# SBC_65C02_ISA_Discrete_v1.net
KiCad netlist of a schematic drawn in EAGLE
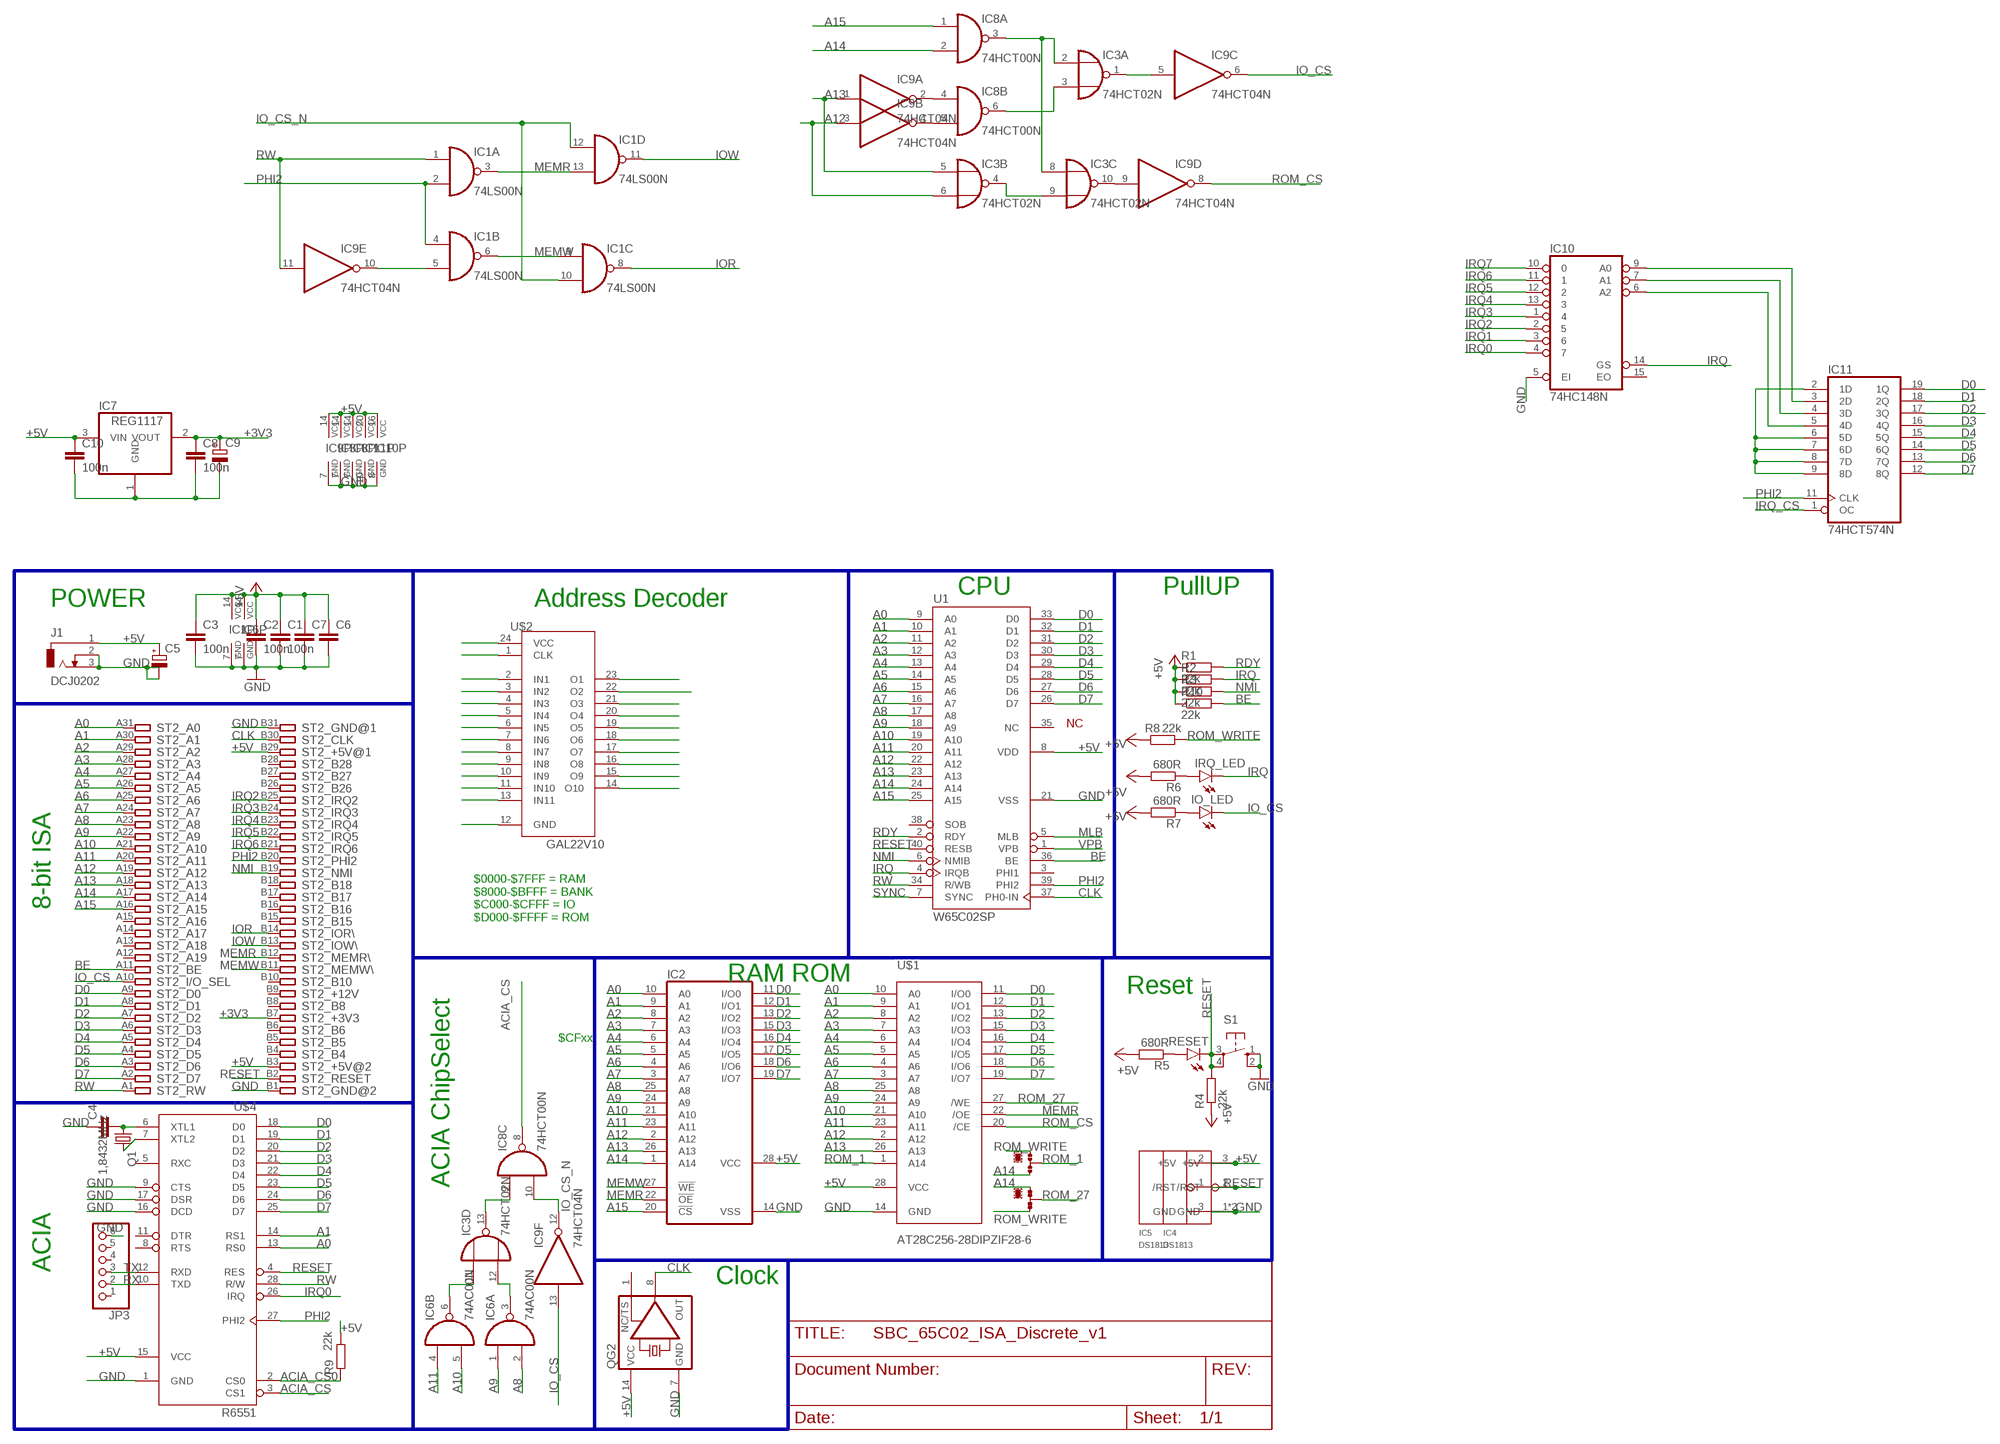
[diagram p0: schematic, sheet 1]

(export (version "E")
  (design (tool "Eeschema 10.0.6"))
  (components
    (comp (ref "C1")
      (value "100n")
      (footprint "eagle-import:C050-025X075")
      (libsource (lib "eagle-import") (part "C-EU050-025X075"))
    )
    (comp (ref "C2")
      (value "100n")
      (footprint "eagle-import:C050-025X075")
      (libsource (lib "eagle-import") (part "C-EU050-025X075"))
    )
    (comp (ref "C3")
      (value "100n")
      (footprint "eagle-import:C050-025X075")
      (libsource (lib "eagle-import") (part "C-EU050-025X075"))
    )
    (comp (ref "C4")
      (value "C-EU025-030X050")
      (footprint "eagle-import:C025-030X050")
      (libsource (lib "eagle-import") (part "rcl_334_C-EU025-030X050"))
    )
    (comp (ref "C5")
      (value "CPOL-EUE3.5-8")
      (footprint "eagle-import:E3,5-8")
      (libsource (lib "eagle-import") (part "CPOL-EUE3.5-8"))
    )
    (comp (ref "C6")
      (value "C-EU050-035X075")
      (footprint "eagle-import:C050-035X075")
      (libsource (lib "eagle-import") (part "rcl_334_C-EU050-035X075"))
    )
    (comp (ref "C7")
      (value "C-EU050-035X075")
      (footprint "eagle-import:C050-035X075")
      (libsource (lib "eagle-import") (part "rcl_334_C-EU050-035X075"))
    )
    (comp (ref "C8")
      (value "100n")
      (footprint "eagle-import:C050-025X075")
      (libsource (lib "eagle-import") (part "C-EU050-025X075"))
    )
    (comp (ref "C9")
      (value "CPOL-EUE3.5-8")
      (footprint "eagle-import:E3,5-8")
      (libsource (lib "eagle-import") (part "CPOL-EUE3.5-8"))
    )
    (comp (ref "C10")
      (value "100n")
      (footprint "eagle-import:C050-025X075")
      (libsource (lib "eagle-import") (part "C-EU050-025X075"))
    )
    (comp (ref "IC1")
      (value "74LS00N")
      (footprint "eagle-import:DIL14")
      (libsource (lib "eagle-import") (part "7400NLS"))
    )
    (comp (ref "IC2")
      (value "62256P")
      (footprint "eagle-import:DIL28-6")
      (libsource (lib "eagle-import") (part "62256P"))
    )
    (comp (ref "IC3")
      (value "74HCT02N")
      (footprint "eagle-import:DIL14")
      (libsource (lib "eagle-import") (part "7402NHCT"))
    )
    (comp (ref "IC4")
      (value "DS1813")
      (footprint "eagle-import:SOT223")
      (libsource (lib "eagle-import") (part "DS1813SOT-223"))
    )
    (comp (ref "IC5")
      (value "DS1813")
      (footprint "eagle-import:TO-92")
      (libsource (lib "eagle-import") (part "DS1813"))
    )
    (comp (ref "IC6")
      (value "74AC00N")
      (footprint "eagle-import:DIL14")
      (libsource (lib "eagle-import") (part "7400NAC"))
    )
    (comp (ref "IC7")
      (value "REG1117")
      (footprint "eagle-import:SOT223")
      (libsource (lib "eagle-import") (part "REG1117"))
    )
    (comp (ref "IC8")
      (value "74HCT00N")
      (footprint "eagle-import:DIL14")
      (libsource (lib "eagle-import") (part "7400NHCT"))
    )
    (comp (ref "IC9")
      (value "74HCT04N")
      (footprint "eagle-import:DIL14")
      (libsource (lib "eagle-import") (part "7404NHCT"))
    )
    (comp (ref "IC10")
      (value "74HC148N")
      (footprint "eagle-import:DIL16")
      (libsource (lib "eagle-import") (part "74148NHC"))
    )
    (comp (ref "IC11")
      (value "74HCT574N")
      (footprint "eagle-import:DIL20")
      (libsource (lib "eagle-import") (part "74574NHCT"))
    )
    (comp (ref "IO_LED")
      (value "LED5MM")
      (footprint "eagle-import:LED5MM")
      (libsource (lib "eagle-import") (part "LED5MM"))
    )
    (comp (ref "IRQ_LED")
      (value "LED5MM")
      (footprint "eagle-import:LED5MM")
      (libsource (lib "eagle-import") (part "LED5MM"))
    )
    (comp (ref "J1")
      (value "DCJ0202")
      (footprint "eagle-import:DCJ0202")
      (libsource (lib "eagle-import") (part "DCJ0202"))
    )
    (comp (ref "JP3")
      (value "PINHD-1X6/90")
      (footprint "eagle-import:1X06_90")
      (libsource (lib "eagle-import") (part "PINHD-1X6/90"))
    )
    (comp (ref "Q1")
      (value "1,8432MHz")
      (footprint "eagle-import:HC49_S")
      (libsource (lib "eagle-import") (part "CRYSTALHC49S"))
    )
    (comp (ref "QG2")
      (value "XO-14")
      (footprint "eagle-import:DIL14S")
      (libsource (lib "eagle-import") (part "XO-14"))
    )
    (comp (ref "R1")
      (value "22k")
      (footprint "eagle-import:0207_10")
      (libsource (lib "eagle-import") (part "R-EU_0207/10"))
    )
    (comp (ref "R2")
      (value "22k")
      (footprint "eagle-import:0207_10")
      (libsource (lib "eagle-import") (part "R-EU_0207/10"))
    )
    (comp (ref "R3")
      (value "22k")
      (footprint "eagle-import:0207_10")
      (libsource (lib "eagle-import") (part "R-EU_0207/10"))
    )
    (comp (ref "R4")
      (value "22k")
      (footprint "eagle-import:0207_10")
      (libsource (lib "eagle-import") (part "resistor_348_R-EU_0207/10"))
    )
    (comp (ref "R5")
      (value "680R")
      (footprint "eagle-import:0207_10")
      (libsource (lib "eagle-import") (part "resistor_348_R-EU_0207/10"))
    )
    (comp (ref "R6")
      (value "680R")
      (footprint "eagle-import:0207_10")
      (libsource (lib "eagle-import") (part "resistor_348_R-EU_0207/10"))
    )
    (comp (ref "R7")
      (value "680R")
      (footprint "eagle-import:0207_10")
      (libsource (lib "eagle-import") (part "resistor_348_R-EU_0207/10"))
    )
    (comp (ref "R8")
      (value "22k")
      (footprint "eagle-import:0207_10")
      (libsource (lib "eagle-import") (part "rcl_334_R-EU_0207/10"))
    )
    (comp (ref "R9")
      (value "22k")
      (footprint "eagle-import:0207_10")
      (libsource (lib "eagle-import") (part "rcl_334_R-EU_0207/10"))
    )
    (comp (ref "R10")
      (value "22k")
      (footprint "eagle-import:0207_10")
      (libsource (lib "eagle-import") (part "R-EU_0207/10"))
    )
    (comp (ref "RESET")
      (value "LED5MM")
      (footprint "eagle-import:LED5MM")
      (libsource (lib "eagle-import") (part "LED5MM"))
    )
    (comp (ref "ROM_1")
      (value "0R-JUMPA")
      (footprint "eagle-import:A0R-JMP")
      (libsource (lib "eagle-import") (part "0R-JUMPA"))
    )
    (comp (ref "ROM_27")
      (value "0R-JUMPA")
      (footprint "eagle-import:A0R-JMP")
      (libsource (lib "eagle-import") (part "0R-JUMPA"))
    )
    (comp (ref "S1")
      (value "10-XX")
      (footprint "eagle-import:B3F-10XX")
      (fields (field (name "MPN") "B3F-1000"))
      (libsource (lib "eagle-import") (part "10-XX"))
    )
    (comp (ref "ST2")
      (value "IBM8BIT_ISA")
      (footprint "eagle-import:IBM8BIT")
      (libsource (lib "eagle-import") (part "IBM8BIT_ISA"))
    )
    (comp (ref "U$1")
      (value "AT28C256-28DIPZIF28-6")
      (footprint "eagle-import:228-1277-00-0602J")
      (libsource (lib "eagle-import") (part "AT28C256-28DIPZIF28-6"))
    )
    (comp (ref "U$2")
      (value "GAL22V10")
      (footprint "eagle-import:DIL28_1")
      (libsource (lib "eagle-import") (part "GAL22V10"))
    )
    (comp (ref "U$4")
      (value "R6551")
      (footprint "eagle-import:DIP-28")
      (libsource (lib "eagle-import") (part "R6551"))
    )
    (comp (ref "U1")
      (value "W65C02SP")
      (footprint "eagle-import:DIP-40")
      (libsource (lib "eagle-import") (part "W65C02SP"))
    )
  )
  (nets
    (net (code "1") (name "+5V") (class "Default")
      (node (ref "C1") (pin "1") (pinfunction "1_1") (pintype "passive"))
      (node (ref "C10") (pin "1") (pinfunction "1_1") (pintype "passive"))
      (node (ref "C2") (pin "1") (pinfunction "1_1") (pintype "passive"))
      (node (ref "C3") (pin "1") (pinfunction "1_1") (pintype "passive"))
      (node (ref "C5") (pin "+") (pinfunction "+_+") (pintype "passive"))
      (node (ref "C6") (pin "1") (pinfunction "1_1") (pintype "passive"))
      (node (ref "C7") (pin "1") (pinfunction "1_1") (pintype "passive"))
      (node (ref "IC1") (pin "14") (pinfunction "VCC_14") (pintype "power_in"))
      (node (ref "IC10") (pin "16") (pinfunction "VCC_16") (pintype "power_in"))
      (node (ref "IC11") (pin "20") (pinfunction "VCC_20") (pintype "power_in"))
      (node (ref "IC2") (pin "28") (pinfunction "VCC_28") (pintype "power_in"))
      (node (ref "IC3") (pin "14") (pinfunction "VCC_14") (pintype "power_in"))
      (node (ref "IC4") (pin "3") (pinfunction "+5V_3") (pintype "power_in"))
      (node (ref "IC5") (pin "2") (pinfunction "+5V_2") (pintype "power_in"))
      (node (ref "IC6") (pin "14") (pinfunction "VCC_14") (pintype "power_in"))
      (node (ref "IC7") (pin "3") (pinfunction "VIN_3") (pintype "input"))
      (node (ref "IC8") (pin "14") (pinfunction "VCC_14") (pintype "power_in"))
      (node (ref "IC9") (pin "14") (pinfunction "VCC_14") (pintype "power_in"))
      (node (ref "J1") (pin "1") (pinfunction "1_1") (pintype "passive"))
      (node (ref "QG2") (pin "14") (pinfunction "VCC_14") (pintype "power_in"))
      (node (ref "R1") (pin "1") (pinfunction "1_1") (pintype "passive"))
      (node (ref "R10") (pin "1") (pinfunction "1_1") (pintype "passive"))
      (node (ref "R2") (pin "1") (pinfunction "1_1") (pintype "passive"))
      (node (ref "R3") (pin "1") (pinfunction "1_1") (pintype "passive"))
      (node (ref "R4") (pin "1") (pinfunction "1_1") (pintype "passive"))
      (node (ref "R5") (pin "2") (pinfunction "2_2") (pintype "passive"))
      (node (ref "R6") (pin "2") (pinfunction "2_2") (pintype "passive"))
      (node (ref "R7") (pin "2") (pinfunction "2_2") (pintype "passive"))
      (node (ref "R8") (pin "1") (pinfunction "1_1") (pintype "passive"))
      (node (ref "R9") (pin "2") (pinfunction "2_2") (pintype "passive"))
      (node (ref "ST2") (pin "B29") (pinfunction "P_B29") (pintype "bidirectional"))
      (node (ref "ST2") (pin "B3") (pinfunction "P_B3") (pintype "bidirectional"))
      (node (ref "U$1") (pin "28") (pinfunction "VCC_28") (pintype "bidirectional"))
      (node (ref "U$4") (pin "15") (pinfunction "VCC_15") (pintype "power_in"))
      (node (ref "U1") (pin "8") (pinfunction "VDD_8") (pintype "power_in"))
    )
    (net (code "2") (name "/+3V3") (class "Default")
      (node (ref "C8") (pin "1") (pinfunction "1_1") (pintype "passive"))
      (node (ref "C9") (pin "+") (pinfunction "+_+") (pintype "passive"))
      (node (ref "IC7") (pin "2") (pinfunction "VOUT_2") (pintype "output"))
      (node (ref "ST2") (pin "B7") (pinfunction "P_B7") (pintype "bidirectional"))
    )
    (net (code "3") (name "/A0") (class "Default")
      (node (ref "IC2") (pin "10") (pinfunction "A0_10") (pintype "input"))
      (node (ref "ST2") (pin "A31") (pinfunction "P_A31") (pintype "bidirectional"))
      (node (ref "U$1") (pin "10") (pinfunction "A0_10") (pintype "bidirectional"))
      (node (ref "U$4") (pin "13") (pinfunction "RS0_13") (pintype "input"))
      (node (ref "U1") (pin "9") (pinfunction "A0_9") (pintype "bidirectional"))
    )
    (net (code "4") (name "/A1") (class "Default")
      (node (ref "IC2") (pin "9") (pinfunction "A1_9") (pintype "input"))
      (node (ref "ST2") (pin "A30") (pinfunction "P_A30") (pintype "bidirectional"))
      (node (ref "U$1") (pin "9") (pinfunction "A1_9") (pintype "bidirectional"))
      (node (ref "U$4") (pin "14") (pinfunction "RS1_14") (pintype "input"))
      (node (ref "U1") (pin "10") (pinfunction "A1_10") (pintype "bidirectional"))
    )
    (net (code "5") (name "/A2") (class "Default")
      (node (ref "IC2") (pin "8") (pinfunction "A2_8") (pintype "input"))
      (node (ref "ST2") (pin "A29") (pinfunction "P_A29") (pintype "bidirectional"))
      (node (ref "U$1") (pin "8") (pinfunction "A2_8") (pintype "bidirectional"))
      (node (ref "U1") (pin "11") (pinfunction "A2_11") (pintype "bidirectional"))
    )
    (net (code "6") (name "/A3") (class "Default")
      (node (ref "IC2") (pin "7") (pinfunction "A3_7") (pintype "input"))
      (node (ref "ST2") (pin "A28") (pinfunction "P_A28") (pintype "bidirectional"))
      (node (ref "U$1") (pin "7") (pinfunction "A3_7") (pintype "bidirectional"))
      (node (ref "U1") (pin "12") (pinfunction "A3_12") (pintype "bidirectional"))
    )
    (net (code "7") (name "/A4") (class "Default")
      (node (ref "IC2") (pin "6") (pinfunction "A4_6") (pintype "input"))
      (node (ref "ST2") (pin "A27") (pinfunction "P_A27") (pintype "bidirectional"))
      (node (ref "U$1") (pin "6") (pinfunction "A4_6") (pintype "bidirectional"))
      (node (ref "U1") (pin "13") (pinfunction "A4_13") (pintype "bidirectional"))
    )
    (net (code "8") (name "/A5") (class "Default")
      (node (ref "IC2") (pin "5") (pinfunction "A5_5") (pintype "input"))
      (node (ref "ST2") (pin "A26") (pinfunction "P_A26") (pintype "bidirectional"))
      (node (ref "U$1") (pin "5") (pinfunction "A5_5") (pintype "bidirectional"))
      (node (ref "U1") (pin "14") (pinfunction "A5_14") (pintype "bidirectional"))
    )
    (net (code "9") (name "/A6") (class "Default")
      (node (ref "IC2") (pin "4") (pinfunction "A6_4") (pintype "input"))
      (node (ref "ST2") (pin "A25") (pinfunction "P_A25") (pintype "bidirectional"))
      (node (ref "U$1") (pin "4") (pinfunction "A6_4") (pintype "bidirectional"))
      (node (ref "U1") (pin "15") (pinfunction "A6_15") (pintype "bidirectional"))
    )
    (net (code "10") (name "/A7") (class "Default")
      (node (ref "IC2") (pin "3") (pinfunction "A7_3") (pintype "input"))
      (node (ref "ST2") (pin "A24") (pinfunction "P_A24") (pintype "bidirectional"))
      (node (ref "U$1") (pin "3") (pinfunction "A7_3") (pintype "bidirectional"))
      (node (ref "U1") (pin "16") (pinfunction "A7_16") (pintype "bidirectional"))
    )
    (net (code "11") (name "/A8") (class "Default")
      (node (ref "IC2") (pin "25") (pinfunction "A8_25") (pintype "input"))
      (node (ref "IC6") (pin "2") (pinfunction "I1_2") (pintype "input"))
      (node (ref "ST2") (pin "A23") (pinfunction "P_A23") (pintype "bidirectional"))
      (node (ref "U$1") (pin "25") (pinfunction "A8_25") (pintype "bidirectional"))
      (node (ref "U1") (pin "17") (pinfunction "A8_17") (pintype "bidirectional"))
    )
    (net (code "12") (name "/A9") (class "Default")
      (node (ref "IC2") (pin "24") (pinfunction "A9_24") (pintype "input"))
      (node (ref "IC6") (pin "1") (pinfunction "I0_1") (pintype "input"))
      (node (ref "ST2") (pin "A22") (pinfunction "P_A22") (pintype "bidirectional"))
      (node (ref "U$1") (pin "24") (pinfunction "A9_24") (pintype "bidirectional"))
      (node (ref "U1") (pin "18") (pinfunction "A9_18") (pintype "bidirectional"))
    )
    (net (code "13") (name "/A10") (class "Default")
      (node (ref "IC2") (pin "21") (pinfunction "A10_21") (pintype "input"))
      (node (ref "IC6") (pin "5") (pinfunction "I1_5") (pintype "input"))
      (node (ref "ST2") (pin "A21") (pinfunction "P_A21") (pintype "bidirectional"))
      (node (ref "U$1") (pin "21") (pinfunction "A10_21") (pintype "bidirectional"))
      (node (ref "U1") (pin "19") (pinfunction "A10_19") (pintype "bidirectional"))
    )
    (net (code "14") (name "/A11") (class "Default")
      (node (ref "IC2") (pin "23") (pinfunction "A11_23") (pintype "input"))
      (node (ref "IC6") (pin "4") (pinfunction "I0_4") (pintype "input"))
      (node (ref "ST2") (pin "A20") (pinfunction "P_A20") (pintype "bidirectional"))
      (node (ref "U$1") (pin "23") (pinfunction "A11_23") (pintype "bidirectional"))
      (node (ref "U1") (pin "20") (pinfunction "A11_20") (pintype "bidirectional"))
    )
    (net (code "15") (name "/A12") (class "Default")
      (node (ref "IC2") (pin "2") (pinfunction "A12_2") (pintype "input"))
      (node (ref "IC3") (pin "6") (pinfunction "I1_6") (pintype "input"))
      (node (ref "IC9") (pin "3") (pinfunction "I_3") (pintype "input"))
      (node (ref "ST2") (pin "A19") (pinfunction "P_A19") (pintype "bidirectional"))
      (node (ref "U$1") (pin "2") (pinfunction "A12_2") (pintype "bidirectional"))
      (node (ref "U1") (pin "22") (pinfunction "A12_22") (pintype "bidirectional"))
    )
    (net (code "16") (name "/A13") (class "Default")
      (node (ref "IC2") (pin "26") (pinfunction "A13_26") (pintype "input"))
      (node (ref "IC3") (pin "5") (pinfunction "I0_5") (pintype "input"))
      (node (ref "IC9") (pin "1") (pinfunction "I_1") (pintype "input"))
      (node (ref "ST2") (pin "A18") (pinfunction "P_A18") (pintype "bidirectional"))
      (node (ref "U$1") (pin "26") (pinfunction "A13_26") (pintype "bidirectional"))
      (node (ref "U1") (pin "23") (pinfunction "A13_23") (pintype "bidirectional"))
    )
    (net (code "17") (name "/A14") (class "Default")
      (node (ref "IC2") (pin "1") (pinfunction "A14_1") (pintype "input"))
      (node (ref "IC8") (pin "2") (pinfunction "I1_2") (pintype "input"))
      (node (ref "ROM_1") (pin "3") (pinfunction "3_3") (pintype "passive"))
      (node (ref "ROM_27") (pin "1") (pinfunction "1_1") (pintype "passive"))
      (node (ref "ST2") (pin "A17") (pinfunction "P_A17") (pintype "bidirectional"))
      (node (ref "U1") (pin "24") (pinfunction "A14_24") (pintype "bidirectional"))
    )
    (net (code "18") (name "/A15") (class "Default")
      (node (ref "IC2") (pin "20") (pinfunction "~{CS}_20") (pintype "input"))
      (node (ref "IC8") (pin "1") (pinfunction "I0_1") (pintype "input"))
      (node (ref "ST2") (pin "A16") (pinfunction "P_A16") (pintype "bidirectional"))
      (node (ref "U1") (pin "25") (pinfunction "A15_25") (pintype "bidirectional"))
    )
    (net (code "19") (name "/ACIA_CS") (class "Default")
      (node (ref "IC8") (pin "8") (pinfunction "O_8") (pintype "output"))
      (node (ref "U$4") (pin "3") (pinfunction "CS1_3") (pintype "input"))
    )
    (net (code "20") (name "/ACIA_CS0") (class "Default")
      (node (ref "R9") (pin "1") (pinfunction "1_1") (pintype "passive"))
      (node (ref "U$4") (pin "2") (pinfunction "CS0_2") (pintype "input"))
    )
    (net (code "21") (name "/BE") (class "Default")
      (node (ref "R10") (pin "2") (pinfunction "2_2") (pintype "passive"))
      (node (ref "ST2") (pin "A11") (pinfunction "P_A11") (pintype "bidirectional"))
      (node (ref "U1") (pin "36") (pinfunction "BE_36") (pintype "input"))
    )
    (net (code "22") (name "/CLK") (class "Default")
      (node (ref "QG2") (pin "8") (pinfunction "OUT_8") (pintype "output"))
      (node (ref "ST2") (pin "B30") (pinfunction "P_B30") (pintype "bidirectional"))
      (node (ref "U1") (pin "37") (pinfunction "PH0-IN_37") (pintype "input"))
    )
    (net (code "23") (name "/D0") (class "Default")
      (node (ref "IC11") (pin "19") (pinfunction "1Q_19") (pintype "tri_state"))
      (node (ref "IC2") (pin "11") (pinfunction "I/O0_11") (pintype "bidirectional"))
      (node (ref "ST2") (pin "A9") (pinfunction "P_A9") (pintype "bidirectional"))
      (node (ref "U$1") (pin "11") (pinfunction "I/O0_11") (pintype "bidirectional"))
      (node (ref "U$4") (pin "18") (pinfunction "D0_18") (pintype "bidirectional"))
      (node (ref "U1") (pin "33") (pinfunction "D0_33") (pintype "bidirectional"))
    )
    (net (code "24") (name "/D1") (class "Default")
      (node (ref "IC11") (pin "18") (pinfunction "2Q_18") (pintype "tri_state"))
      (node (ref "IC2") (pin "12") (pinfunction "I/O1_12") (pintype "bidirectional"))
      (node (ref "ST2") (pin "A8") (pinfunction "P_A8") (pintype "bidirectional"))
      (node (ref "U$1") (pin "12") (pinfunction "I/O1_12") (pintype "bidirectional"))
      (node (ref "U$4") (pin "19") (pinfunction "D1_19") (pintype "bidirectional"))
      (node (ref "U1") (pin "32") (pinfunction "D1_32") (pintype "bidirectional"))
    )
    (net (code "25") (name "/D2") (class "Default")
      (node (ref "IC11") (pin "17") (pinfunction "3Q_17") (pintype "tri_state"))
      (node (ref "IC2") (pin "13") (pinfunction "I/O2_13") (pintype "bidirectional"))
      (node (ref "ST2") (pin "A7") (pinfunction "P_A7") (pintype "bidirectional"))
      (node (ref "U$1") (pin "13") (pinfunction "I/O2_13") (pintype "bidirectional"))
      (node (ref "U$4") (pin "20") (pinfunction "D2_20") (pintype "bidirectional"))
      (node (ref "U1") (pin "31") (pinfunction "D2_31") (pintype "bidirectional"))
    )
    (net (code "26") (name "/D3") (class "Default")
      (node (ref "IC11") (pin "16") (pinfunction "4Q_16") (pintype "tri_state"))
      (node (ref "IC2") (pin "15") (pinfunction "I/O3_15") (pintype "bidirectional"))
      (node (ref "ST2") (pin "A6") (pinfunction "P_A6") (pintype "bidirectional"))
      (node (ref "U$1") (pin "15") (pinfunction "I/O3_15") (pintype "bidirectional"))
      (node (ref "U$4") (pin "21") (pinfunction "D3_21") (pintype "bidirectional"))
      (node (ref "U1") (pin "30") (pinfunction "D3_30") (pintype "bidirectional"))
    )
    (net (code "27") (name "/D4") (class "Default")
      (node (ref "IC11") (pin "15") (pinfunction "5Q_15") (pintype "tri_state"))
      (node (ref "IC2") (pin "16") (pinfunction "I/O4_16") (pintype "bidirectional"))
      (node (ref "ST2") (pin "A5") (pinfunction "P_A5") (pintype "bidirectional"))
      (node (ref "U$1") (pin "16") (pinfunction "I/O4_16") (pintype "bidirectional"))
      (node (ref "U$4") (pin "22") (pinfunction "D4_22") (pintype "bidirectional"))
      (node (ref "U1") (pin "29") (pinfunction "D4_29") (pintype "bidirectional"))
    )
    (net (code "28") (name "/D5") (class "Default")
      (node (ref "IC11") (pin "14") (pinfunction "6Q_14") (pintype "tri_state"))
      (node (ref "IC2") (pin "17") (pinfunction "I/O5_17") (pintype "bidirectional"))
      (node (ref "ST2") (pin "A4") (pinfunction "P_A4") (pintype "bidirectional"))
      (node (ref "U$1") (pin "17") (pinfunction "I/O5_17") (pintype "bidirectional"))
      (node (ref "U$4") (pin "23") (pinfunction "D5_23") (pintype "bidirectional"))
      (node (ref "U1") (pin "28") (pinfunction "D5_28") (pintype "bidirectional"))
    )
    (net (code "29") (name "/D6") (class "Default")
      (node (ref "IC11") (pin "13") (pinfunction "7Q_13") (pintype "tri_state"))
      (node (ref "IC2") (pin "18") (pinfunction "I/O6_18") (pintype "bidirectional"))
      (node (ref "ST2") (pin "A3") (pinfunction "P_A3") (pintype "bidirectional"))
      (node (ref "U$1") (pin "18") (pinfunction "I/O6_18") (pintype "bidirectional"))
      (node (ref "U$4") (pin "24") (pinfunction "D6_24") (pintype "bidirectional"))
      (node (ref "U1") (pin "27") (pinfunction "D6_27") (pintype "bidirectional"))
    )
    (net (code "30") (name "/D7") (class "Default")
      (node (ref "IC11") (pin "12") (pinfunction "8Q_12") (pintype "tri_state"))
      (node (ref "IC2") (pin "19") (pinfunction "I/O7_19") (pintype "bidirectional"))
      (node (ref "ST2") (pin "A2") (pinfunction "P_A2") (pintype "bidirectional"))
      (node (ref "U$1") (pin "19") (pinfunction "I/O7_19") (pintype "bidirectional"))
      (node (ref "U$4") (pin "25") (pinfunction "D7_25") (pintype "bidirectional"))
      (node (ref "U1") (pin "26") (pinfunction "D7_26") (pintype "bidirectional"))
    )
    (net (code "31") (name "/IOR") (class "Default")
      (node (ref "IC1") (pin "8") (pinfunction "O_8") (pintype "output"))
      (node (ref "ST2") (pin "B14") (pinfunction "P_B14") (pintype "bidirectional"))
    )
    (net (code "32") (name "/IOW") (class "Default")
      (node (ref "IC1") (pin "11") (pinfunction "O_11") (pintype "output"))
      (node (ref "ST2") (pin "B13") (pinfunction "P_B13") (pintype "bidirectional"))
    )
    (net (code "33") (name "/IO_CS") (class "Default")
      (node (ref "IC9") (pin "13") (pinfunction "I_13") (pintype "input"))
      (node (ref "IC9") (pin "6") (pinfunction "O_6") (pintype "output"))
      (node (ref "IO_LED") (pin "K") (pinfunction "C_K") (pintype "passive"))
      (node (ref "ST2") (pin "A10") (pinfunction "P_A10") (pintype "bidirectional"))
    )
    (net (code "34") (name "/IO_CS_N") (class "Default")
      (node (ref "IC1") (pin "10") (pinfunction "I1_10") (pintype "input"))
      (node (ref "IC1") (pin "12") (pinfunction "I0_12") (pintype "input"))
      (node (ref "IC8") (pin "10") (pinfunction "I1_10") (pintype "input"))
      (node (ref "IC9") (pin "12") (pinfunction "O_12") (pintype "output"))
    )
    (net (code "35") (name "/IRQ") (class "Default")
      (node (ref "IC10") (pin "14") (pinfunction "GS_14") (pintype "output"))
      (node (ref "IRQ_LED") (pin "K") (pinfunction "C_K") (pintype "passive"))
      (node (ref "R2") (pin "2") (pinfunction "2_2") (pintype "passive"))
      (node (ref "U1") (pin "4") (pinfunction "IRQB_4") (pintype "input"))
    )
    (net (code "36") (name "/IRQ0") (class "Default")
      (node (ref "IC10") (pin "4") (pinfunction "7_4") (pintype "input"))
      (node (ref "U$4") (pin "26") (pinfunction "IRQ_26") (pintype "output"))
    )
    (net (code "37") (name "/IRQ1") (class "Default")
      (node (ref "IC10") (pin "3") (pinfunction "6_3") (pintype "input"))
    )
    (net (code "38") (name "/IRQ2") (class "Default")
      (node (ref "IC10") (pin "2") (pinfunction "5_2") (pintype "input"))
      (node (ref "ST2") (pin "B25") (pinfunction "P_B25") (pintype "bidirectional"))
    )
    (net (code "39") (name "/IRQ3") (class "Default")
      (node (ref "IC10") (pin "1") (pinfunction "4_1") (pintype "input"))
      (node (ref "ST2") (pin "B24") (pinfunction "P_B24") (pintype "bidirectional"))
    )
    (net (code "40") (name "/IRQ4") (class "Default")
      (node (ref "IC10") (pin "13") (pinfunction "3_13") (pintype "input"))
      (node (ref "ST2") (pin "B23") (pinfunction "P_B23") (pintype "bidirectional"))
    )
    (net (code "41") (name "/IRQ5") (class "Default")
      (node (ref "IC10") (pin "12") (pinfunction "2_12") (pintype "input"))
      (node (ref "ST2") (pin "B22") (pinfunction "P_B22") (pintype "bidirectional"))
    )
    (net (code "42") (name "/IRQ6") (class "Default")
      (node (ref "IC10") (pin "11") (pinfunction "1_11") (pintype "input"))
      (node (ref "ST2") (pin "B21") (pinfunction "P_B21") (pintype "bidirectional"))
    )
    (net (code "43") (name "/IRQ7") (class "Default")
      (node (ref "IC10") (pin "10") (pinfunction "0_10") (pintype "input"))
    )
    (net (code "44") (name "/IRQ_CS") (class "Default")
      (node (ref "IC11") (pin "1") (pinfunction "OC_1") (pintype "input"))
    )
    (net (code "45") (name "/MEMR") (class "Default")
      (node (ref "IC1") (pin "13") (pinfunction "I1_13") (pintype "input"))
      (node (ref "IC1") (pin "3") (pinfunction "O_3") (pintype "output"))
      (node (ref "IC2") (pin "22") (pinfunction "~{OE}_22") (pintype "input"))
      (node (ref "ST2") (pin "B12") (pinfunction "P_B12") (pintype "bidirectional"))
      (node (ref "U$1") (pin "22") (pinfunction "/OE_22") (pintype "bidirectional"))
    )
    (net (code "46") (name "/MEMW") (class "Default")
      (node (ref "IC1") (pin "6") (pinfunction "O_6") (pintype "output"))
      (node (ref "IC1") (pin "9") (pinfunction "I0_9") (pintype "input"))
      (node (ref "IC2") (pin "27") (pinfunction "~{WE}_27") (pintype "input"))
      (node (ref "ST2") (pin "B11") (pinfunction "P_B11") (pintype "bidirectional"))
    )
    (net (code "47") (name "/MLB") (class "Default")
      (node (ref "U1") (pin "5") (pinfunction "MLB_5") (pintype "output"))
    )
    (net (code "48") (name "/NMI") (class "Default")
      (node (ref "R3") (pin "2") (pinfunction "2_2") (pintype "passive"))
      (node (ref "ST2") (pin "B19") (pinfunction "P_B19") (pintype "bidirectional"))
      (node (ref "U1") (pin "6") (pinfunction "NMIB_6") (pintype "input"))
    )
    (net (code "49") (name "/PHI2") (class "Default")
      (node (ref "IC1") (pin "2") (pinfunction "I1_2") (pintype "input"))
      (node (ref "IC1") (pin "4") (pinfunction "I0_4") (pintype "input"))
      (node (ref "IC11") (pin "11") (pinfunction "CLK_11") (pintype "input"))
      (node (ref "ST2") (pin "B20") (pinfunction "P_B20") (pintype "bidirectional"))
      (node (ref "U$4") (pin "27") (pinfunction "PHI2_27") (pintype "input"))
      (node (ref "U1") (pin "39") (pinfunction "PHI2_39") (pintype "output"))
    )
    (net (code "50") (name "/RDY") (class "Default")
      (node (ref "R1") (pin "2") (pinfunction "2_2") (pintype "passive"))
      (node (ref "U1") (pin "2") (pinfunction "RDY_2") (pintype "bidirectional"))
    )
    (net (code "51") (name "/RESET") (class "Default")
      (node (ref "IC4") (pin "2") (pinfunction "/RST_2") (pintype "passive"))
      (node (ref "IC5") (pin "1") (pinfunction "/RST_1") (pintype "passive"))
      (node (ref "R4") (pin "2") (pinfunction "2_2") (pintype "passive"))
      (node (ref "RESET") (pin "K") (pinfunction "C_K") (pintype "passive"))
      (node (ref "S1") (pin "3") (pinfunction "P_3") (pintype "passive"))
      (node (ref "S1") (pin "4") (pinfunction "P1_4") (pintype "passive"))
      (node (ref "ST2") (pin "B2") (pinfunction "P_B2") (pintype "bidirectional"))
      (node (ref "U$4") (pin "4") (pinfunction "RES_4") (pintype "input"))
      (node (ref "U1") (pin "40") (pinfunction "RESB_40") (pintype "input"))
    )
    (net (code "52") (name "/ROM_1") (class "Default")
      (node (ref "ROM_1") (pin "2") (pinfunction "2_2") (pintype "passive"))
      (node (ref "U$1") (pin "1") (pinfunction "A14_1") (pintype "bidirectional"))
    )
    (net (code "53") (name "/ROM_27") (class "Default")
      (node (ref "ROM_27") (pin "2") (pinfunction "2_2") (pintype "passive"))
      (node (ref "U$1") (pin "27") (pinfunction "/WE_27") (pintype "bidirectional"))
    )
    (net (code "54") (name "/ROM_CS") (class "Default")
      (node (ref "IC9") (pin "8") (pinfunction "O_8") (pintype "output"))
      (node (ref "U$1") (pin "20") (pinfunction "/CE_20") (pintype "bidirectional"))
    )
    (net (code "55") (name "/ROM_WRITE") (class "Default")
      (node (ref "R8") (pin "2") (pinfunction "2_2") (pintype "passive"))
      (node (ref "ROM_1") (pin "1") (pinfunction "1_1") (pintype "passive"))
      (node (ref "ROM_27") (pin "3") (pinfunction "3_3") (pintype "passive"))
    )
    (net (code "56") (name "/RW") (class "Default")
      (node (ref "IC1") (pin "1") (pinfunction "I0_1") (pintype "input"))
      (node (ref "IC9") (pin "11") (pinfunction "I_11") (pintype "input"))
      (node (ref "ST2") (pin "A1") (pinfunction "P_A1") (pintype "bidirectional"))
      (node (ref "U$4") (pin "28") (pinfunction "R/W_28") (pintype "input"))
      (node (ref "U1") (pin "34") (pinfunction "R/WB_34") (pintype "output"))
    )
    (net (code "57") (name "/RX") (class "Default")
      (node (ref "JP3") (pin "2") (pinfunction "2_2") (pintype "passive"))
      (node (ref "U$4") (pin "10") (pinfunction "TXD_10") (pintype "output"))
    )
    (net (code "58") (name "/SYNC") (class "Default")
      (node (ref "U1") (pin "7") (pinfunction "SYNC_7") (pintype "output"))
    )
    (net (code "59") (name "/TX") (class "Default")
      (node (ref "JP3") (pin "3") (pinfunction "3_3") (pintype "passive"))
      (node (ref "U$4") (pin "12") (pinfunction "RXD_12") (pintype "input"))
    )
    (net (code "60") (name "/VPB") (class "Default")
      (node (ref "U1") (pin "1") (pinfunction "VPB_1") (pintype "output"))
    )
    (net (code "61") (name "GND") (class "Default")
      (node (ref "C1") (pin "2") (pinfunction "2_2") (pintype "passive"))
      (node (ref "C2") (pin "2") (pinfunction "2_2") (pintype "passive"))
      (node (ref "C3") (pin "2") (pinfunction "2_2") (pintype "passive"))
      (node (ref "C4") (pin "1") (pinfunction "1_1") (pintype "passive"))
      (node (ref "C5") (pin "-") (pinfunction "-_-") (pintype "passive"))
      (node (ref "C6") (pin "2") (pinfunction "2_2") (pintype "passive"))
      (node (ref "C7") (pin "2") (pinfunction "2_2") (pintype "passive"))
      (node (ref "IC1") (pin "7") (pinfunction "GND_7") (pintype "power_in"))
      (node (ref "IC10") (pin "5") (pinfunction "EI_5") (pintype "input"))
      (node (ref "IC10") (pin "8") (pinfunction "GND_8") (pintype "power_in"))
      (node (ref "IC11") (pin "10") (pinfunction "GND_10") (pintype "power_in"))
      (node (ref "IC2") (pin "14") (pinfunction "VSS_14") (pintype "power_in"))
      (node (ref "IC3") (pin "7") (pinfunction "GND_7") (pintype "power_in"))
      (node (ref "IC4") (pin "1") (pinfunction "GND_1") (pintype "power_in"))
      (node (ref "IC4") (pin "4") (pinfunction "GND_4") (pintype "power_in"))
      (node (ref "IC5") (pin "3") (pinfunction "GND_3") (pintype "power_in"))
      (node (ref "IC6") (pin "7") (pinfunction "GND_7") (pintype "power_in"))
      (node (ref "IC8") (pin "7") (pinfunction "GND_7") (pintype "power_in"))
      (node (ref "IC9") (pin "7") (pinfunction "GND_7") (pintype "power_in"))
      (node (ref "J1") (pin "2") (pinfunction "2_2") (pintype "passive"))
      (node (ref "J1") (pin "3") (pinfunction "3_3") (pintype "passive"))
      (node (ref "JP3") (pin "6") (pinfunction "6_6") (pintype "passive"))
      (node (ref "QG2") (pin "7") (pinfunction "GND_7") (pintype "power_in"))
      (node (ref "S1") (pin "1") (pinfunction "S_1") (pintype "passive"))
      (node (ref "S1") (pin "2") (pinfunction "S1_2") (pintype "passive"))
      (node (ref "ST2") (pin "B1") (pinfunction "P_B1") (pintype "bidirectional"))
      (node (ref "ST2") (pin "B31") (pinfunction "P_B31") (pintype "bidirectional"))
      (node (ref "U$1") (pin "14") (pinfunction "GND_14") (pintype "bidirectional"))
      (node (ref "U$4") (pin "1") (pinfunction "GND_1") (pintype "power_in"))
      (node (ref "U$4") (pin "16") (pinfunction "DCD_16") (pintype "input"))
      (node (ref "U$4") (pin "17") (pinfunction "DSR_17") (pintype "input"))
      (node (ref "U$4") (pin "9") (pinfunction "CTS_9") (pintype "input"))
      (node (ref "U1") (pin "21") (pinfunction "VSS_21") (pintype "power_in"))
    )
    (net (code "62") (name "Net-(IC1B-I1)") (class "Default")
      (node (ref "IC1") (pin "5") (pinfunction "I1_5") (pintype "input"))
      (node (ref "IC9") (pin "10") (pinfunction "O_10") (pintype "output"))
    )
    (net (code "63") (name "Net-(IC3A-I0)") (class "Default")
      (node (ref "IC3") (pin "2") (pinfunction "I0_2") (pintype "input"))
      (node (ref "IC3") (pin "8") (pinfunction "I0_8") (pintype "input"))
      (node (ref "IC8") (pin "3") (pinfunction "O_3") (pintype "output"))
    )
    (net (code "64") (name "Net-(IC3A-I1)") (class "Default")
      (node (ref "IC3") (pin "3") (pinfunction "I1_3") (pintype "input"))
      (node (ref "IC8") (pin "6") (pinfunction "O_6") (pintype "output"))
    )
    (net (code "65") (name "Net-(IC3A-O)") (class "Default")
      (node (ref "IC3") (pin "1") (pinfunction "O_1") (pintype "output"))
      (node (ref "IC9") (pin "5") (pinfunction "I_5") (pintype "input"))
    )
    (net (code "66") (name "Net-(IC3B-O)") (class "Default")
      (node (ref "IC3") (pin "4") (pinfunction "O_4") (pintype "output"))
      (node (ref "IC3") (pin "9") (pinfunction "I1_9") (pintype "input"))
    )
    (net (code "67") (name "Net-(IC3C-O)") (class "Default")
      (node (ref "IC3") (pin "10") (pinfunction "O_10") (pintype "output"))
      (node (ref "IC9") (pin "9") (pinfunction "I_9") (pintype "input"))
    )
    (net (code "68") (name "Net-(IC3D-I0)") (class "Default")
      (node (ref "IC3") (pin "11") (pinfunction "I0_11") (pintype "input"))
      (node (ref "IC6") (pin "6") (pinfunction "O_6") (pintype "output"))
    )
    (net (code "69") (name "Net-(IC3D-I1)") (class "Default")
      (node (ref "IC3") (pin "12") (pinfunction "I1_12") (pintype "input"))
      (node (ref "IC6") (pin "3") (pinfunction "O_3") (pintype "output"))
    )
    (net (code "70") (name "Net-(IC3D-O)") (class "Default")
      (node (ref "IC3") (pin "13") (pinfunction "O_13") (pintype "output"))
      (node (ref "IC8") (pin "9") (pinfunction "I0_9") (pintype "input"))
    )
    (net (code "71") (name "Net-(IC7-GND)") (class "Default")
      (node (ref "C10") (pin "2") (pinfunction "2_2") (pintype "passive"))
      (node (ref "C8") (pin "2") (pinfunction "2_2") (pintype "passive"))
      (node (ref "C9") (pin "-") (pinfunction "-_-") (pintype "passive"))
      (node (ref "IC7") (pin "1") (pinfunction "GND_1") (pintype "power_in"))
    )
    (net (code "72") (name "Net-(IC8B-I0)") (class "Default")
      (node (ref "IC8") (pin "4") (pinfunction "I0_4") (pintype "input"))
      (node (ref "IC9") (pin "2") (pinfunction "O_2") (pintype "output"))
    )
    (net (code "73") (name "Net-(IC8B-I1)") (class "Default")
      (node (ref "IC8") (pin "5") (pinfunction "I1_5") (pintype "input"))
      (node (ref "IC9") (pin "4") (pinfunction "O_4") (pintype "output"))
    )
    (net (code "74") (name "Net-(IC10A-A0)") (class "Default")
      (node (ref "IC10") (pin "9") (pinfunction "A0_9") (pintype "output"))
      (node (ref "IC11") (pin "3") (pinfunction "2D_3") (pintype "input"))
    )
    (net (code "75") (name "Net-(IC10A-A1)") (class "Default")
      (node (ref "IC10") (pin "7") (pinfunction "A1_7") (pintype "output"))
      (node (ref "IC11") (pin "4") (pinfunction "3D_4") (pintype "input"))
    )
    (net (code "76") (name "Net-(IC10A-A2)") (class "Default")
      (node (ref "IC10") (pin "6") (pinfunction "A2_6") (pintype "output"))
      (node (ref "IC11") (pin "5") (pinfunction "4D_5") (pintype "input"))
    )
    (net (code "77") (name "Net-(IC11A-1D)") (class "Default")
      (node (ref "IC11") (pin "2") (pinfunction "1D_2") (pintype "input"))
      (node (ref "IC11") (pin "6") (pinfunction "5D_6") (pintype "input"))
      (node (ref "IC11") (pin "7") (pinfunction "6D_7") (pintype "input"))
      (node (ref "IC11") (pin "8") (pinfunction "7D_8") (pintype "input"))
      (node (ref "IC11") (pin "9") (pinfunction "8D_9") (pintype "input"))
    )
    (net (code "78") (name "Net-(IO_LED-PadA)") (class "Default")
      (node (ref "IO_LED") (pin "A") (pinfunction "A_A") (pintype "passive"))
      (node (ref "R7") (pin "1") (pinfunction "1_1") (pintype "passive"))
    )
    (net (code "79") (name "Net-(IRQ_LED-PadA)") (class "Default")
      (node (ref "IRQ_LED") (pin "A") (pinfunction "A_A") (pintype "passive"))
      (node (ref "R6") (pin "1") (pinfunction "1_1") (pintype "passive"))
    )
    (net (code "80") (name "Net-(R5-Pad1)") (class "Default")
      (node (ref "R5") (pin "1") (pinfunction "1_1") (pintype "passive"))
      (node (ref "RESET") (pin "A") (pinfunction "A_A") (pintype "passive"))
    )
    (net (code "81") (name "Net-(U$4-XTL1)") (class "Default")
      (node (ref "C4") (pin "2") (pinfunction "2_2") (pintype "passive"))
      (node (ref "Q1") (pin "1") (pinfunction "1_1") (pintype "passive"))
      (node (ref "U$4") (pin "6") (pinfunction "XTL1_6") (pintype "input"))
    )
    (net (code "82") (name "Net-(U$4-XTL2)") (class "Default")
      (node (ref "Q1") (pin "2") (pinfunction "2_2") (pintype "passive"))
      (node (ref "U$4") (pin "7") (pinfunction "XTL2_7") (pintype "output"))
    )
    (net (code "83") (name "unconnected-(IC10A-EO-Pad15)") (class "Default")
      (node (ref "IC10") (pin "15") (pinfunction "EO_15") (pintype "output"))
    )
    (net (code "84") (name "unconnected-(JP3-Pad1)") (class "Default")
      (node (ref "JP3") (pin "1") (pinfunction "1_1") (pintype "passive"))
    )
    (net (code "85") (name "unconnected-(JP3-Pad4)") (class "Default")
      (node (ref "JP3") (pin "4") (pinfunction "4_4") (pintype "passive"))
    )
    (net (code "86") (name "unconnected-(JP3-Pad5)") (class "Default")
      (node (ref "JP3") (pin "5") (pinfunction "5_5") (pintype "passive"))
    )
    (net (code "87") (name "unconnected-(QG2-TS-Pad1)") (class "Default")
      (node (ref "QG2") (pin "1") (pinfunction "TS_1") (pintype "passive"))
    )
    (net (code "88") (name "unconnected-(ST2A-P-PadB9)") (class "Default")
      (node (ref "ST2") (pin "B9") (pinfunction "P_B9") (pintype "bidirectional"))
    )
    (net (code "89") (name "unconnected-(ST2AA-P-PadB16)") (class "Default")
      (node (ref "ST2") (pin "B16") (pinfunction "P_B16") (pintype "bidirectional"))
    )
    (net (code "90") (name "unconnected-(ST2AB-P-PadB17)") (class "Default")
      (node (ref "ST2") (pin "B17") (pinfunction "P_B17") (pintype "bidirectional"))
    )
    (net (code "91") (name "unconnected-(ST2AC-P-PadB18)") (class "Default")
      (node (ref "ST2") (pin "B18") (pinfunction "P_B18") (pintype "bidirectional"))
    )
    (net (code "92") (name "unconnected-(ST2AD-P-PadB26)") (class "Default")
      (node (ref "ST2") (pin "B26") (pinfunction "P_B26") (pintype "bidirectional"))
    )
    (net (code "93") (name "unconnected-(ST2AE-P-PadB27)") (class "Default")
      (node (ref "ST2") (pin "B27") (pinfunction "P_B27") (pintype "bidirectional"))
    )
    (net (code "94") (name "unconnected-(ST2AF-P-PadB28)") (class "Default")
      (node (ref "ST2") (pin "B28") (pinfunction "P_B28") (pintype "bidirectional"))
    )
    (net (code "95") (name "unconnected-(ST2AG-P-PadB4)") (class "Default")
      (node (ref "ST2") (pin "B4") (pinfunction "P_B4") (pintype "bidirectional"))
    )
    (net (code "96") (name "unconnected-(ST2AH-P-PadB5)") (class "Default")
      (node (ref "ST2") (pin "B5") (pinfunction "P_B5") (pintype "bidirectional"))
    )
    (net (code "97") (name "unconnected-(ST2AI-P-PadB6)") (class "Default")
      (node (ref "ST2") (pin "B6") (pinfunction "P_B6") (pintype "bidirectional"))
    )
    (net (code "98") (name "unconnected-(ST2AJ-P-PadB8)") (class "Default")
      (node (ref "ST2") (pin "B8") (pinfunction "P_B8") (pintype "bidirectional"))
    )
    (net (code "99") (name "unconnected-(ST2M-P-PadA15)") (class "Default")
      (node (ref "ST2") (pin "A15") (pinfunction "P_A15") (pintype "bidirectional"))
    )
    (net (code "100") (name "unconnected-(ST2N-P-PadA14)") (class "Default")
      (node (ref "ST2") (pin "A14") (pinfunction "P_A14") (pintype "bidirectional"))
    )
    (net (code "101") (name "unconnected-(ST2O-P-PadA13)") (class "Default")
      (node (ref "ST2") (pin "A13") (pinfunction "P_A13") (pintype "bidirectional"))
    )
    (net (code "102") (name "unconnected-(ST2P-P-PadA12)") (class "Default")
      (node (ref "ST2") (pin "A12") (pinfunction "P_A12") (pintype "bidirectional"))
    )
    (net (code "103") (name "unconnected-(ST2Y-P-PadB10)") (class "Default")
      (node (ref "ST2") (pin "B10") (pinfunction "P_B10") (pintype "bidirectional"))
    )
    (net (code "104") (name "unconnected-(ST2Z-P-PadB15)") (class "Default")
      (node (ref "ST2") (pin "B15") (pinfunction "P_B15") (pintype "bidirectional"))
    )
    (net (code "105") (name "unconnected-(U$2-CLK-Pad1)") (class "Default")
      (node (ref "U$2") (pin "1") (pinfunction "CLK_1") (pintype "bidirectional"))
    )
    (net (code "106") (name "unconnected-(U$2-GND-Pad12)") (class "Default")
      (node (ref "U$2") (pin "12") (pinfunction "GND_12") (pintype "bidirectional"))
    )
    (net (code "107") (name "unconnected-(U$2-IN1-Pad2)") (class "Default")
      (node (ref "U$2") (pin "2") (pinfunction "IN1_2") (pintype "bidirectional"))
    )
    (net (code "108") (name "unconnected-(U$2-IN2-Pad3)") (class "Default")
      (node (ref "U$2") (pin "3") (pinfunction "IN2_3") (pintype "bidirectional"))
    )
    (net (code "109") (name "unconnected-(U$2-IN3-Pad4)") (class "Default")
      (node (ref "U$2") (pin "4") (pinfunction "IN3_4") (pintype "bidirectional"))
    )
    (net (code "110") (name "unconnected-(U$2-IN4-Pad5)") (class "Default")
      (node (ref "U$2") (pin "5") (pinfunction "IN4_5") (pintype "bidirectional"))
    )
    (net (code "111") (name "unconnected-(U$2-IN5-Pad6)") (class "Default")
      (node (ref "U$2") (pin "6") (pinfunction "IN5_6") (pintype "bidirectional"))
    )
    (net (code "112") (name "unconnected-(U$2-IN6-Pad7)") (class "Default")
      (node (ref "U$2") (pin "7") (pinfunction "IN6_7") (pintype "bidirectional"))
    )
    (net (code "113") (name "unconnected-(U$2-IN7-Pad8)") (class "Default")
      (node (ref "U$2") (pin "8") (pinfunction "IN7_8") (pintype "bidirectional"))
    )
    (net (code "114") (name "unconnected-(U$2-IN8-Pad9)") (class "Default")
      (node (ref "U$2") (pin "9") (pinfunction "IN8_9") (pintype "bidirectional"))
    )
    (net (code "115") (name "unconnected-(U$2-IN9-Pad10)") (class "Default")
      (node (ref "U$2") (pin "10") (pinfunction "IN9_10") (pintype "bidirectional"))
    )
    (net (code "116") (name "unconnected-(U$2-IN10-Pad11)") (class "Default")
      (node (ref "U$2") (pin "11") (pinfunction "IN10_11") (pintype "bidirectional"))
    )
    (net (code "117") (name "unconnected-(U$2-IN11-Pad13)") (class "Default")
      (node (ref "U$2") (pin "13") (pinfunction "IN11_13") (pintype "bidirectional"))
    )
    (net (code "118") (name "unconnected-(U$2-O1-Pad23)") (class "Default")
      (node (ref "U$2") (pin "23") (pinfunction "O1_23") (pintype "bidirectional"))
    )
    (net (code "119") (name "unconnected-(U$2-O2-Pad22)") (class "Default")
      (node (ref "U$2") (pin "22") (pinfunction "O2_22") (pintype "bidirectional"))
    )
    (net (code "120") (name "unconnected-(U$2-O3-Pad21)") (class "Default")
      (node (ref "U$2") (pin "21") (pinfunction "O3_21") (pintype "bidirectional"))
    )
    (net (code "121") (name "unconnected-(U$2-O4-Pad20)") (class "Default")
      (node (ref "U$2") (pin "20") (pinfunction "O4_20") (pintype "bidirectional"))
    )
    (net (code "122") (name "unconnected-(U$2-O5-Pad19)") (class "Default")
      (node (ref "U$2") (pin "19") (pinfunction "O5_19") (pintype "bidirectional"))
    )
    (net (code "123") (name "unconnected-(U$2-O6-Pad18)") (class "Default")
      (node (ref "U$2") (pin "18") (pinfunction "O6_18") (pintype "bidirectional"))
    )
    (net (code "124") (name "unconnected-(U$2-O7-Pad17)") (class "Default")
      (node (ref "U$2") (pin "17") (pinfunction "O7_17") (pintype "bidirectional"))
    )
    (net (code "125") (name "unconnected-(U$2-O8-Pad16)") (class "Default")
      (node (ref "U$2") (pin "16") (pinfunction "O8_16") (pintype "bidirectional"))
    )
    (net (code "126") (name "unconnected-(U$2-O9-Pad15)") (class "Default")
      (node (ref "U$2") (pin "15") (pinfunction "O9_15") (pintype "bidirectional"))
    )
    (net (code "127") (name "unconnected-(U$2-O10-Pad14)") (class "Default")
      (node (ref "U$2") (pin "14") (pinfunction "O10_14") (pintype "bidirectional"))
    )
    (net (code "128") (name "unconnected-(U$2-VCC-Pad24)") (class "Default")
      (node (ref "U$2") (pin "24") (pinfunction "VCC_24") (pintype "bidirectional"))
    )
    (net (code "129") (name "unconnected-(U$4-DTR-Pad11)") (class "Default")
      (node (ref "U$4") (pin "11") (pinfunction "DTR_11") (pintype "output"))
    )
    (net (code "130") (name "unconnected-(U$4-RTS-Pad8)") (class "Default")
      (node (ref "U$4") (pin "8") (pinfunction "RTS_8") (pintype "output"))
    )
    (net (code "131") (name "unconnected-(U$4-RXC-Pad5)") (class "Default")
      (node (ref "U$4") (pin "5") (pinfunction "RXC_5") (pintype "bidirectional"))
    )
    (net (code "132") (name "unconnected-(U1-NC-Pad35)") (class "Default")
      (node (ref "U1") (pin "35") (pinfunction "NC_35") (pintype "no_connect"))
    )
    (net (code "133") (name "unconnected-(U1-PHI1-Pad3)") (class "Default")
      (node (ref "U1") (pin "3") (pinfunction "PHI1_3") (pintype "output"))
    )
    (net (code "134") (name "unconnected-(U1-SOB-Pad38)") (class "Default")
      (node (ref "U1") (pin "38") (pinfunction "SOB_38") (pintype "input"))
    )
  )
)
